# 1-Schematic_example_channel.net
KiCad netlist of a schematic drawn in EasyEDA
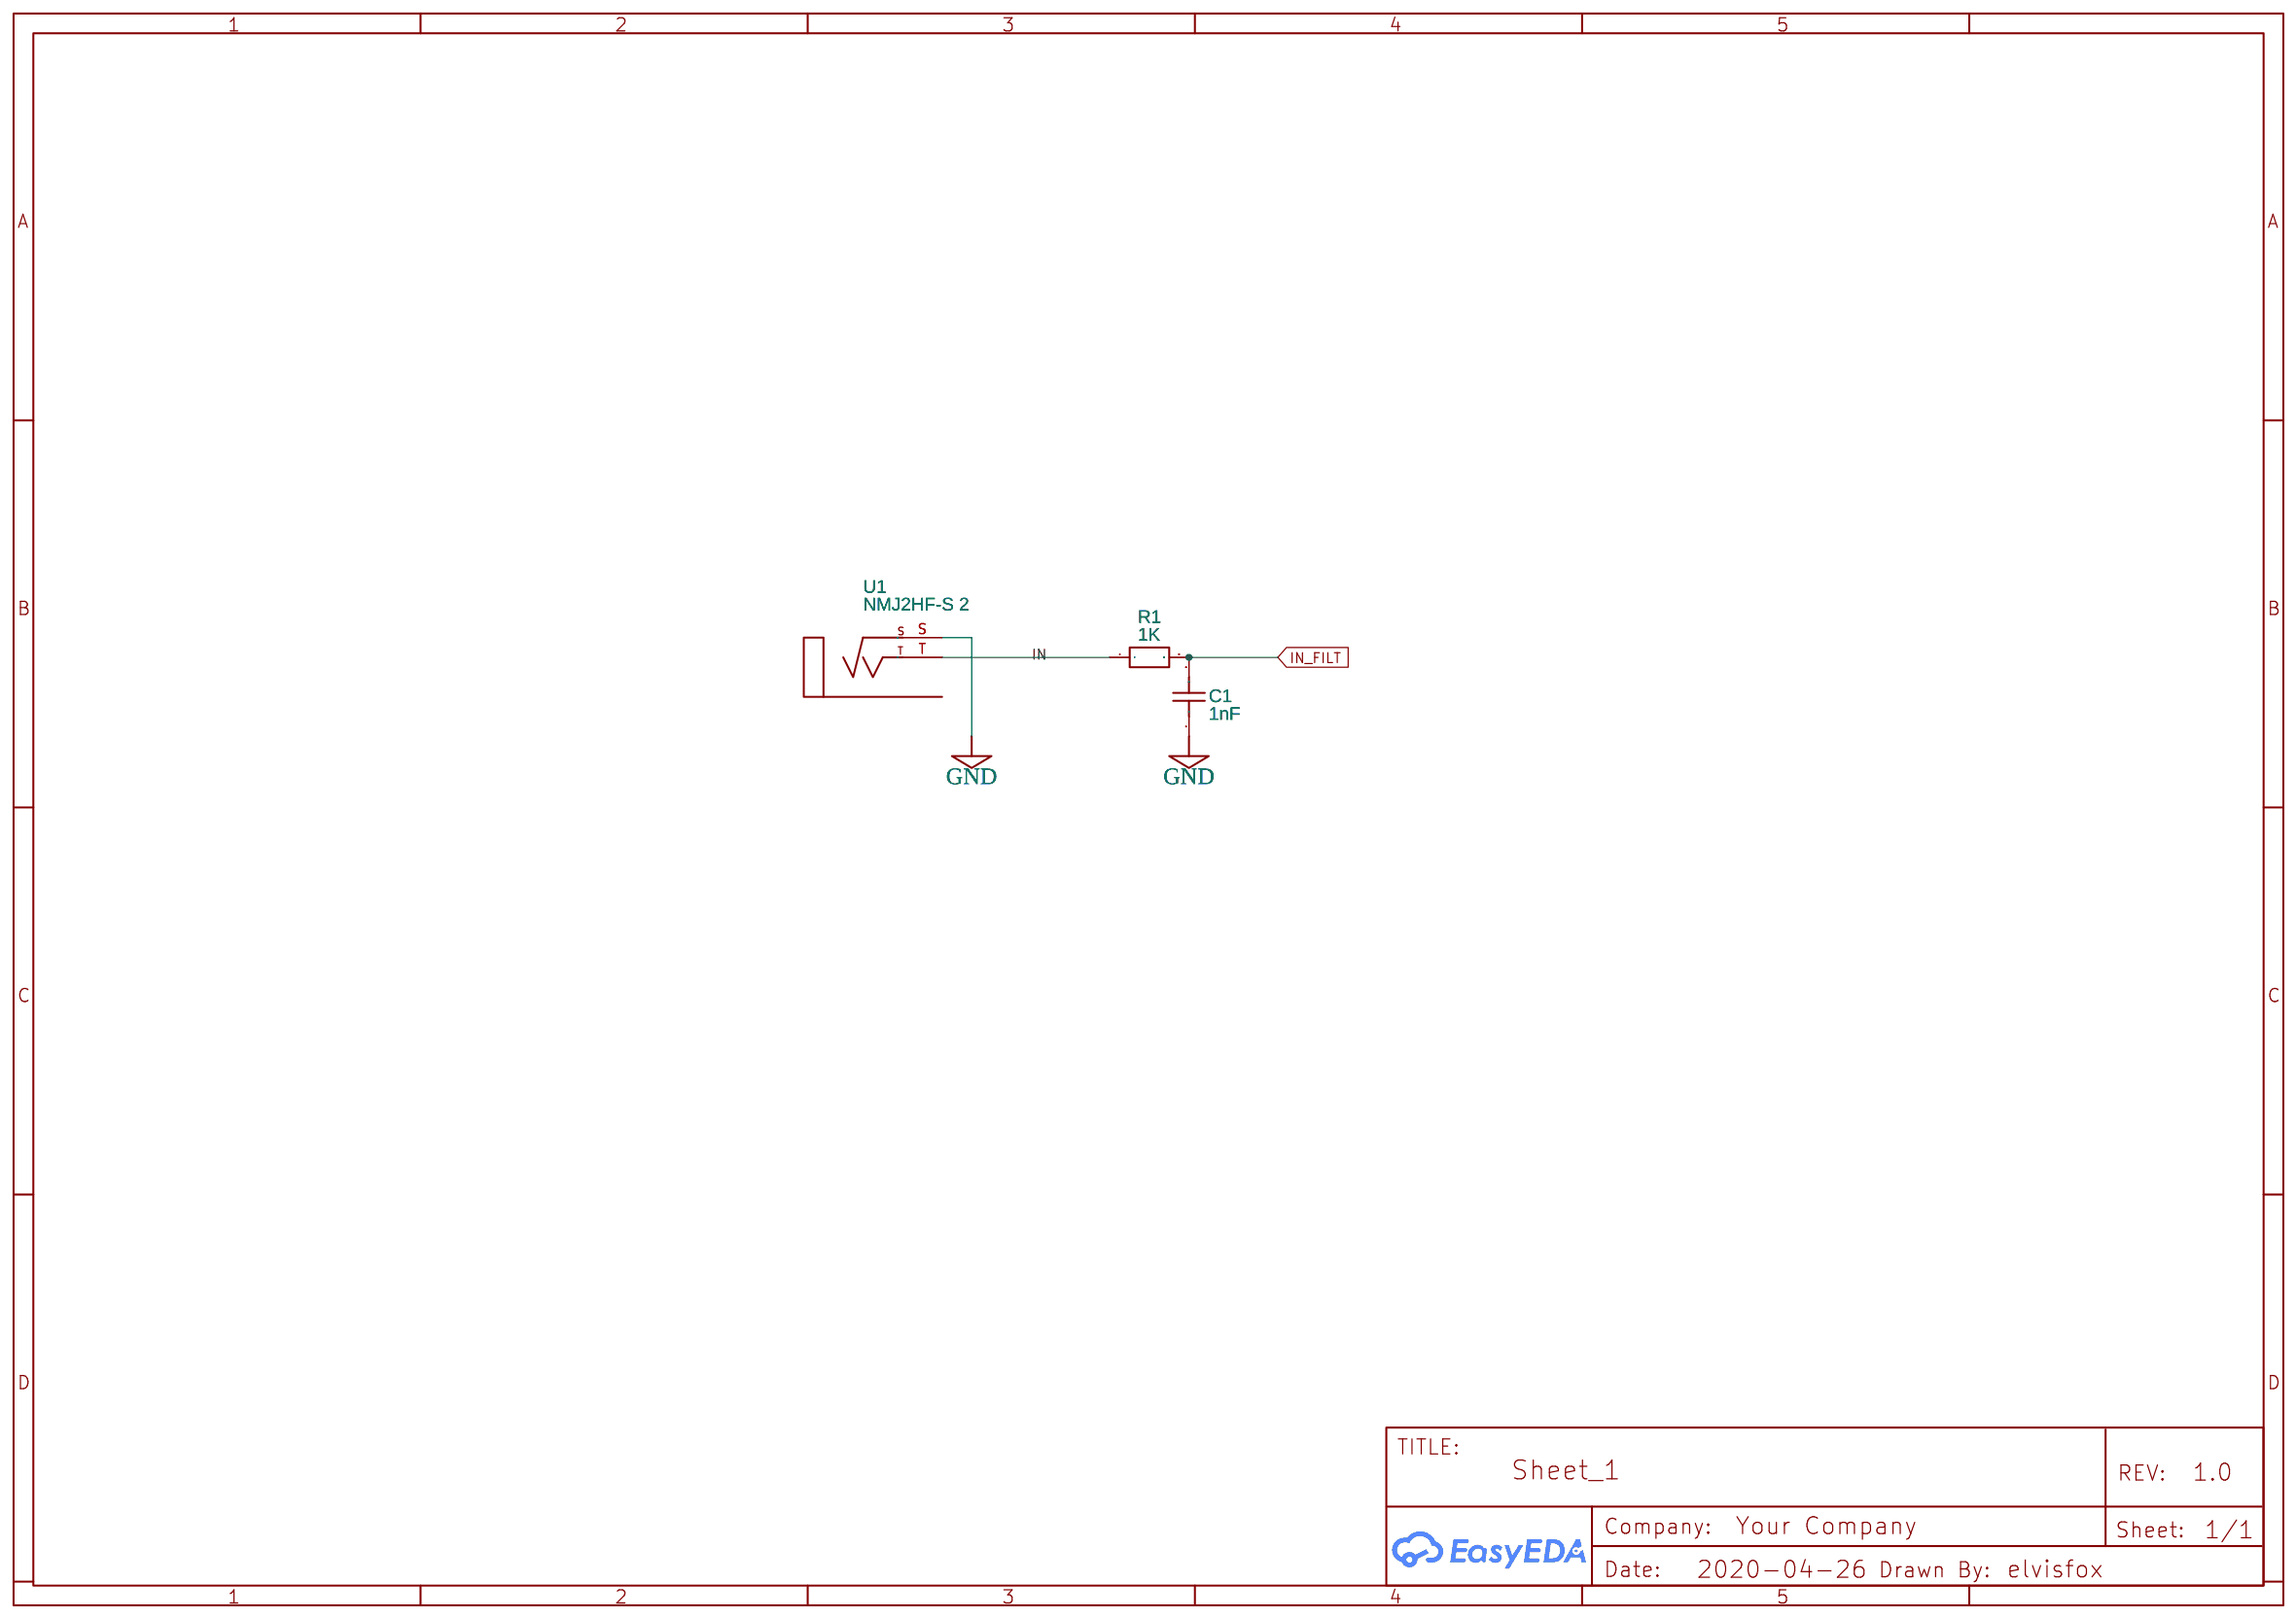
[diagram p0: schematic sheet]

(export (version "E")
  (design (tool "Eeschema 10.0.6"))
  (components
    (comp (ref "C1")
      (value "1nF")
      (fields
        (field (name "BOM_Manufacturer Part") "GRM1882C1H102JA01D")
        (field (name "BOM_Supplier Part") "C85968")
      )
      (libsource (lib "") (part "GRM1882C1H102JA01D"))
    )
    (comp (ref "R1")
      (value "1K")
      (fields
        (field (name "BOM_Manufacturer Part") "PTFR0603B1K00N9")
        (field (name "BOM_Supplier Part") "C394536")
      )
      (libsource (lib "") (part "PTFR0603B1K00N9"))
    )
    (comp (ref "U1") (value "NMJ2HF-S 2") (libsource (lib "") (part "NMJ2HF-S 2")))
  )
  (nets
    (net (code "1") (name "/IN") (class "Default")
      (node (ref "R1") (pin "1") (pinfunction "1_1") (pintype "unspecified"))
      (node (ref "U1") (pin "T") (pinfunction "T_T") (pintype "unspecified"))
    )
    (net (code "2") (name "GND") (class "Default")
      (node (ref "C1") (pin "1") (pinfunction "1_1") (pintype "unspecified"))
      (node (ref "U1") (pin "S") (pinfunction "S_S") (pintype "unspecified"))
    )
    (net (code "3") (name "IN_FILT") (class "Default")
      (node (ref "C1") (pin "2") (pinfunction "2_2") (pintype "unspecified"))
      (node (ref "R1") (pin "2") (pinfunction "2_2") (pintype "unspecified"))
    )
  )
)
